# sensordoline.net
KiCad netlist of a schematic drawn in Altium Designer
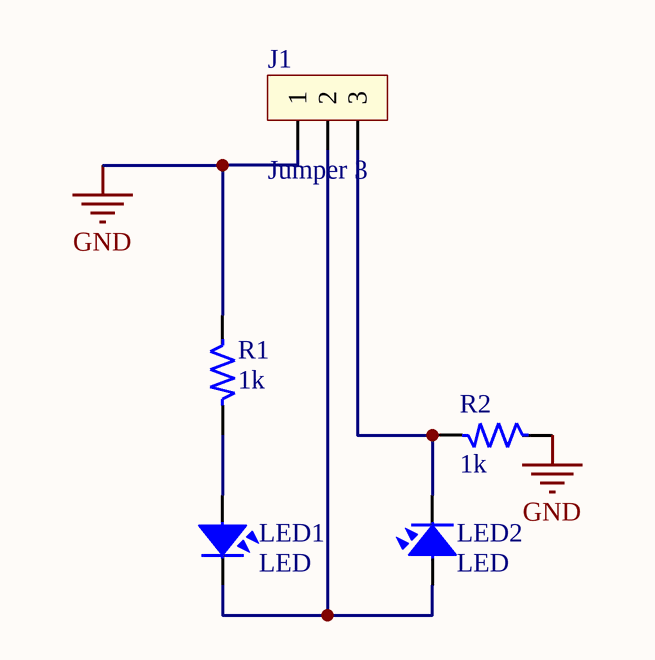
[diagram p0: sensordoline.SchDoc]

(export (version "E")
  (design (tool "Eeschema 10.0.6"))
  (components
    (comp (ref "J1") (value "Jumper 3") (footprint "JP3") (libsource (lib "My Library") (part "JP3")))
    (comp (ref "LED1")
      (value "LED")
      (footprint "LED-3")
      (description "LED Single colour Green and Red")
      (libsource (lib "My Library") (part "LED"))
    )
    (comp (ref "LED2")
      (value "LED")
      (footprint "LED-3")
      (description "LED Single colour Green and Red")
      (libsource (lib "My Library") (part "LED"))
    )
    (comp (ref "R1")
      (value "1k")
      (footprint "RES-SMD-0805")
      (description "Resistor 1/4W")
      (libsource (lib "My Library") (part "R"))
    )
    (comp (ref "R2")
      (value "1k")
      (footprint "RES-SMD-0805")
      (description "Resistor 1/4W")
      (libsource (lib "My Library") (part "R"))
    )
  )
  (nets
    (net (code "1") (name "GND") (class "Default")
      (node (ref "J1") (pin "1") (pinfunction "1_1") (pintype "passive"))
      (node (ref "R1") (pin "1") (pinfunction "1_1") (pintype "passive"))
      (node (ref "R2") (pin "1") (pinfunction "1_1") (pintype "passive"))
    )
    (net (code "2") (name "Net-(J1-Pad2)") (class "Default")
      (node (ref "J1") (pin "2") (pinfunction "2_2") (pintype "passive"))
      (node (ref "LED1") (pin "2") (pinfunction "2_2") (pintype "passive"))
      (node (ref "LED2") (pin "1") (pinfunction "1_1") (pintype "passive"))
    )
    (net (code "3") (name "Net-(J1-Pad3)") (class "Default")
      (node (ref "J1") (pin "3") (pinfunction "3_3") (pintype "passive"))
      (node (ref "LED2") (pin "2") (pinfunction "2_2") (pintype "passive"))
      (node (ref "R2") (pin "2") (pinfunction "2_2") (pintype "passive"))
    )
    (net (code "4") (name "Net-(LED1-Pad1)") (class "Default")
      (node (ref "LED1") (pin "1") (pinfunction "1_1") (pintype "passive"))
      (node (ref "R1") (pin "2") (pinfunction "2_2") (pintype "passive"))
    )
  )
)
